# Adapter_Board.net
KiCad netlist of a schematic drawn in EAGLE
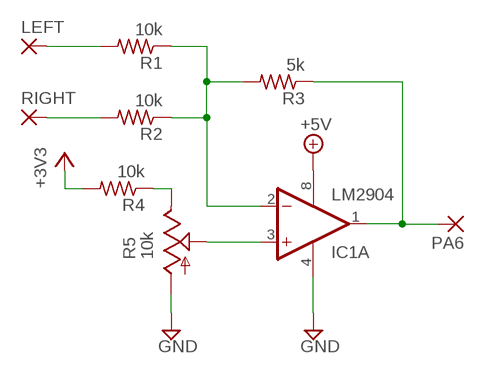
[diagram p0: schematic, sheet 1]

(export (version "E")
  (design (tool "Eeschema 10.0.6"))
  (components
    (comp (ref "IC1")
      (value "LM2904")
      (footprint "eagle-import:DIL08")
      (libsource (lib "eagle-import") (part "LM358N"))
    )
    (comp (ref "LEFT")
      (value "2,54/1,0")
      (footprint "eagle-import:2,54_1,0")
      (libsource (lib "eagle-import") (part "2,54/1,0"))
    )
    (comp (ref "PA6")
      (value "2,54/1,0")
      (footprint "eagle-import:2,54_1,0")
      (libsource (lib "eagle-import") (part "2,54/1,0"))
    )
    (comp (ref "R1")
      (value "10k")
      (footprint "eagle-import:0204_7")
      (libsource (lib "eagle-import") (part "R-US_0204/7"))
    )
    (comp (ref "R2")
      (value "10k")
      (footprint "eagle-import:0204_7")
      (libsource (lib "eagle-import") (part "R-US_0204/7"))
    )
    (comp (ref "R3")
      (value "5k")
      (footprint "eagle-import:0204_7")
      (libsource (lib "eagle-import") (part "R-US_0204/7"))
    )
    (comp (ref "R4")
      (value "10k")
      (footprint "eagle-import:0204_7")
      (libsource (lib "eagle-import") (part "R-US_0204/7"))
    )
    (comp (ref "R5")
      (value "10k")
      (footprint "eagle-import:CA6V")
      (libsource (lib "eagle-import") (part "TRIM_US-CA6V"))
    )
    (comp (ref "RIGHT")
      (value "2,54/1,0")
      (footprint "eagle-import:2,54_1,0")
      (libsource (lib "eagle-import") (part "2,54/1,0"))
    )
  )
  (nets
    (net (code "1") (name "+3V3") (class "Default")
      (node (ref "R4") (pin "2") (pinfunction "2_2") (pintype "passive"))
    )
    (net (code "2") (name "+5V") (class "Default")
      (node (ref "IC1") (pin "8") (pinfunction "V+_8") (pintype "power_in"))
    )
    (net (code "3") (name "GND") (class "Default")
      (node (ref "IC1") (pin "4") (pinfunction "V-_4") (pintype "power_in"))
      (node (ref "R5") (pin "A") (pinfunction "A_A") (pintype "passive"))
    )
    (net (code "4") (name "Net-(IC1A-+IN)") (class "Default")
      (node (ref "IC1") (pin "3") (pinfunction "+IN_3") (pintype "input"))
      (node (ref "R5") (pin "S") (pinfunction "S_S") (pintype "passive"))
    )
    (net (code "5") (name "Net-(IC1A--IN)") (class "Default")
      (node (ref "IC1") (pin "2") (pinfunction "-IN_2") (pintype "input"))
      (node (ref "R1") (pin "1") (pinfunction "1_1") (pintype "passive"))
      (node (ref "R2") (pin "1") (pinfunction "1_1") (pintype "passive"))
      (node (ref "R3") (pin "2") (pinfunction "2_2") (pintype "passive"))
    )
    (net (code "6") (name "Net-(IC1A-OUT)") (class "Default")
      (node (ref "IC1") (pin "1") (pinfunction "OUT_1") (pintype "output"))
      (node (ref "PA6") (pin "1") (pinfunction "P_1") (pintype "passive"))
      (node (ref "R3") (pin "1") (pinfunction "1_1") (pintype "passive"))
    )
    (net (code "7") (name "Net-(LEFT-P)") (class "Default")
      (node (ref "LEFT") (pin "1") (pinfunction "P_1") (pintype "passive"))
      (node (ref "R1") (pin "2") (pinfunction "2_2") (pintype "passive"))
    )
    (net (code "8") (name "Net-(R4-Pad1)") (class "Default")
      (node (ref "R4") (pin "1") (pinfunction "1_1") (pintype "passive"))
      (node (ref "R5") (pin "E") (pinfunction "E_E") (pintype "passive"))
    )
    (net (code "9") (name "Net-(RIGHT-P)") (class "Default")
      (node (ref "R2") (pin "2") (pinfunction "2_2") (pintype "passive"))
      (node (ref "RIGHT") (pin "1") (pinfunction "P_1") (pintype "passive"))
    )
  )
)
